# CCupPSU.net
KiCad netlist of a schematic drawn in EAGLE
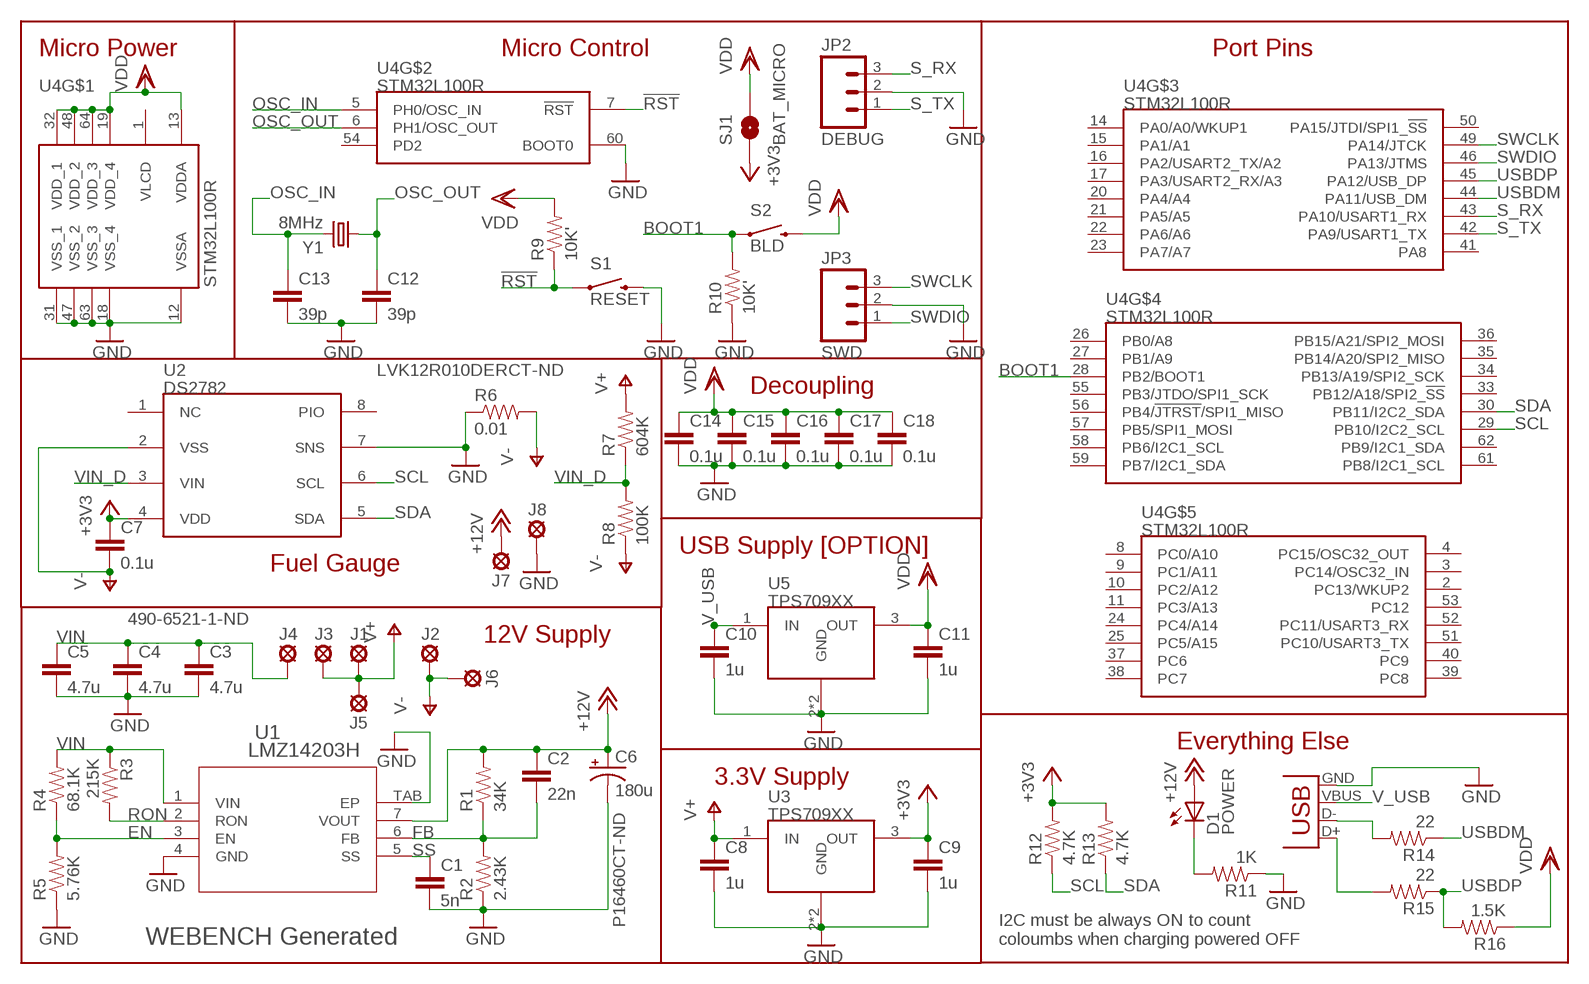
[diagram p0: schematic, sheet 1]

(export (version "E")
  (design (tool "Eeschema 10.0.6"))
  (components
    (comp (ref "C1")
      (value "5n")
      (footprint "eagle-import:1206")
      (libsource (lib "eagle-import") (part "CAP1206"))
    )
    (comp (ref "C2")
      (value "22n")
      (footprint "eagle-import:1206")
      (libsource (lib "eagle-import") (part "CAP1206"))
    )
    (comp (ref "C3")
      (value "4.7u")
      (footprint "eagle-import:1206")
      (libsource (lib "eagle-import") (part "CAP1206"))
    )
    (comp (ref "C4")
      (value "4.7u")
      (footprint "eagle-import:1206")
      (libsource (lib "eagle-import") (part "CAP1206"))
    )
    (comp (ref "C5")
      (value "4.7u")
      (footprint "eagle-import:1206")
      (libsource (lib "eagle-import") (part "CAP1206"))
    )
    (comp (ref "C6")
      (value "180u")
      (footprint "eagle-import:PANASONIC_E")
      (libsource (lib "eagle-import") (part "CAP_POLE"))
    )
    (comp (ref "C7")
      (value "0.1u")
      (footprint "eagle-import:1206")
      (libsource (lib "eagle-import") (part "CAP1206"))
    )
    (comp (ref "C8")
      (value "1u")
      (footprint "eagle-import:1206")
      (libsource (lib "eagle-import") (part "CAP1206"))
    )
    (comp (ref "C9")
      (value "1u")
      (footprint "eagle-import:1206")
      (libsource (lib "eagle-import") (part "CAP1206"))
    )
    (comp (ref "C10")
      (value "1u")
      (footprint "eagle-import:1206")
      (libsource (lib "eagle-import") (part "CAP1206"))
    )
    (comp (ref "C11")
      (value "1u")
      (footprint "eagle-import:1206")
      (libsource (lib "eagle-import") (part "CAP1206"))
    )
    (comp (ref "C12")
      (value "39p")
      (footprint "eagle-import:1206")
      (libsource (lib "eagle-import") (part "CAP1206"))
    )
    (comp (ref "C13")
      (value "39p")
      (footprint "eagle-import:1206")
      (libsource (lib "eagle-import") (part "CAP1206"))
    )
    (comp (ref "C14")
      (value "0.1u")
      (footprint "eagle-import:1206")
      (libsource (lib "eagle-import") (part "CAP1206"))
    )
    (comp (ref "C15")
      (value "0.1u")
      (footprint "eagle-import:1206")
      (libsource (lib "eagle-import") (part "CAP1206"))
    )
    (comp (ref "C16")
      (value "0.1u")
      (footprint "eagle-import:1206")
      (libsource (lib "eagle-import") (part "CAP1206"))
    )
    (comp (ref "C17")
      (value "0.1u")
      (footprint "eagle-import:1206")
      (libsource (lib "eagle-import") (part "CAP1206"))
    )
    (comp (ref "C18")
      (value "0.1u")
      (footprint "eagle-import:1206")
      (libsource (lib "eagle-import") (part "CAP1206"))
    )
    (comp (ref "D1")
      (value "POWER")
      (footprint "eagle-import:LED-1206")
      (libsource (lib "eagle-import") (part "LED-RED1206"))
    )
    (comp (ref "J1")
      (value "SE14")
      (footprint "eagle-import:SE14")
      (libsource (lib "eagle-import") (part "SE14"))
    )
    (comp (ref "J2")
      (value "SE14")
      (footprint "eagle-import:SE14")
      (libsource (lib "eagle-import") (part "SE14"))
    )
    (comp (ref "J3")
      (value "SE14")
      (footprint "eagle-import:SE14")
      (libsource (lib "eagle-import") (part "SE14"))
    )
    (comp (ref "J4")
      (value "SE14")
      (footprint "eagle-import:SE14")
      (libsource (lib "eagle-import") (part "SE14"))
    )
    (comp (ref "J5")
      (value "SE14")
      (footprint "eagle-import:SE14")
      (libsource (lib "eagle-import") (part "SE14"))
    )
    (comp (ref "J6")
      (value "SE14")
      (footprint "eagle-import:SE14")
      (libsource (lib "eagle-import") (part "SE14"))
    )
    (comp (ref "J7")
      (value "SE14")
      (footprint "eagle-import:SE14")
      (libsource (lib "eagle-import") (part "SE14"))
    )
    (comp (ref "J8")
      (value "SE14")
      (footprint "eagle-import:SE14")
      (libsource (lib "eagle-import") (part "SE14"))
    )
    (comp (ref "JP1")
      (value "USBSMD")
      (footprint "eagle-import:USB-MINIB")
      (libsource (lib "eagle-import") (part "USBSMD"))
    )
    (comp (ref "JP2")
      (value "DEBUG")
      (footprint "eagle-import:1X03")
      (libsource (lib "eagle-import") (part "M03PTH"))
    )
    (comp (ref "JP3")
      (value "SWD")
      (footprint "eagle-import:1X03")
      (libsource (lib "eagle-import") (part "M03PTH"))
    )
    (comp (ref "R1")
      (value "34K")
      (footprint "eagle-import:1206")
      (libsource (lib "eagle-import") (part "RESISTOR1206"))
    )
    (comp (ref "R2")
      (value "2.43K")
      (footprint "eagle-import:1206")
      (libsource (lib "eagle-import") (part "RESISTOR1206"))
    )
    (comp (ref "R3")
      (value "215K")
      (footprint "eagle-import:1206")
      (libsource (lib "eagle-import") (part "RESISTOR1206"))
    )
    (comp (ref "R4")
      (value "68.1K")
      (footprint "eagle-import:1206")
      (libsource (lib "eagle-import") (part "RESISTOR1206"))
    )
    (comp (ref "R5")
      (value "5.76K")
      (footprint "eagle-import:1206")
      (libsource (lib "eagle-import") (part "RESISTOR1206"))
    )
    (comp (ref "R6")
      (value "0.01")
      (footprint "eagle-import:1206")
      (libsource (lib "eagle-import") (part "RESISTOR1206"))
    )
    (comp (ref "R7")
      (value "604K")
      (footprint "eagle-import:1206")
      (libsource (lib "eagle-import") (part "RESISTOR1206"))
    )
    (comp (ref "R8")
      (value "100K")
      (footprint "eagle-import:1206")
      (libsource (lib "eagle-import") (part "RESISTOR1206"))
    )
    (comp (ref "R9")
      (value "10K'")
      (footprint "eagle-import:1206")
      (libsource (lib "eagle-import") (part "RESISTOR1206"))
    )
    (comp (ref "R10")
      (value "10K'")
      (footprint "eagle-import:1206")
      (libsource (lib "eagle-import") (part "RESISTOR1206"))
    )
    (comp (ref "R11")
      (value "1K")
      (footprint "eagle-import:1206")
      (libsource (lib "eagle-import") (part "RESISTOR1206"))
    )
    (comp (ref "R12")
      (value "4.7K")
      (footprint "eagle-import:1206")
      (libsource (lib "eagle-import") (part "RESISTOR1206"))
    )
    (comp (ref "R13")
      (value "4.7K")
      (footprint "eagle-import:1206")
      (libsource (lib "eagle-import") (part "RESISTOR1206"))
    )
    (comp (ref "R14")
      (value "22")
      (footprint "eagle-import:1206")
      (libsource (lib "eagle-import") (part "RES1206"))
    )
    (comp (ref "R15")
      (value "22")
      (footprint "eagle-import:1206")
      (libsource (lib "eagle-import") (part "RES1206"))
    )
    (comp (ref "R16")
      (value "1.5K")
      (footprint "eagle-import:1206")
      (libsource (lib "eagle-import") (part "RES1206"))
    )
    (comp (ref "S1")
      (value "RESET")
      (footprint "eagle-import:TACTILE-PTH")
      (libsource (lib "eagle-import") (part "SWITCH-MOMENTARY-2PTH"))
    )
    (comp (ref "S2")
      (value "BLD")
      (footprint "eagle-import:TACTILE-PTH")
      (libsource (lib "eagle-import") (part "SWITCH-MOMENTARY-2PTH"))
    )
    (comp (ref "SJ1")
      (value "BAT_MICRO")
      (footprint "eagle-import:SJ_2S-TRACE")
      (libsource (lib "eagle-import") (part "SOLDERJUMPERTRACE"))
    )
    (comp (ref "U1")
      (value "LMZ14203H")
      (footprint "eagle-import:TZA07A")
      (fields
        (field (name "MANUFACTURER") "Texas Instruments")
        (field (name "MANUFACTURER_PART_NUMBER") "lmz14203h_ndw_7")
      )
      (libsource (lib "eagle-import") (part "LMZ14203H"))
    )
    (comp (ref "U2")
      (value "DS2782")
      (footprint "eagle-import:TSSOP8")
      (libsource (lib "eagle-import") (part "DS2782"))
    )
    (comp (ref "U3")
      (value "TPS709XX")
      (footprint "eagle-import:SOT223")
      (libsource (lib "eagle-import") (part "TPS709XX"))
    )
    (comp (ref "U4")
      (value "STM32L100R")
      (footprint "eagle-import:TQFP64")
      (libsource (lib "eagle-import") (part "STM32L100R"))
    )
    (comp (ref "U5")
      (value "TPS709XX")
      (footprint "eagle-import:SOT223")
      (libsource (lib "eagle-import") (part "TPS709XX"))
    )
    (comp (ref "Y1")
      (value "8MHz")
      (footprint "eagle-import:HC49US")
      (libsource (lib "eagle-import") (part "CRYSTALHC49US"))
    )
  )
  (nets
    (net (code "1") (name "+3V3") (class "Default")
      (node (ref "C7") (pin "1") (pinfunction "1_1") (pintype "passive"))
      (node (ref "C9") (pin "1") (pinfunction "1_1") (pintype "passive"))
      (node (ref "R12") (pin "2") (pinfunction "2_2") (pintype "passive"))
      (node (ref "R13") (pin "2") (pinfunction "2_2") (pintype "passive"))
      (node (ref "SJ1") (pin "1") (pinfunction "1_1") (pintype "passive"))
      (node (ref "U2") (pin "4") (pinfunction "VDD_4") (pintype "power_in"))
      (node (ref "U3") (pin "3") (pinfunction "OUT_3") (pintype "power_in"))
    )
    (net (code "2") (name "+12V") (class "Default")
      (node (ref "C2") (pin "1") (pinfunction "1_1") (pintype "passive"))
      (node (ref "C6") (pin "+") (pinfunction "+_+") (pintype "passive"))
      (node (ref "D1") (pin "A") (pinfunction "A_A") (pintype "passive"))
      (node (ref "J7") (pin "MP") (pinfunction "MP_MP") (pintype "passive"))
      (node (ref "R1") (pin "2") (pinfunction "2_2") (pintype "passive"))
      (node (ref "U1") (pin "7") (pinfunction "VOUT_7") (pintype "power_in"))
    )
    (net (code "3") (name "/BOOT1") (class "Default")
      (node (ref "R10") (pin "2") (pinfunction "2_2") (pintype "passive"))
      (node (ref "S2") (pin "1") (pinfunction "1_1") (pintype "passive"))
      (node (ref "U4") (pin "28") (pinfunction "PB2/BOOT1_28") (pintype "bidirectional"))
    )
    (net (code "4") (name "/EN") (class "Default")
      (node (ref "R4") (pin "1") (pinfunction "1_1") (pintype "passive"))
      (node (ref "R5") (pin "2") (pinfunction "2_2") (pintype "passive"))
      (node (ref "U1") (pin "3") (pinfunction "EN_3") (pintype "input"))
    )
    (net (code "5") (name "/FB") (class "Default")
      (node (ref "C2") (pin "2") (pinfunction "2_2") (pintype "passive"))
      (node (ref "R1") (pin "1") (pinfunction "1_1") (pintype "passive"))
      (node (ref "R2") (pin "2") (pinfunction "2_2") (pintype "passive"))
      (node (ref "U1") (pin "6") (pinfunction "FB_6") (pintype "output"))
    )
    (net (code "6") (name "/OSC_IN") (class "Default")
      (node (ref "C13") (pin "1") (pinfunction "1_1") (pintype "passive"))
      (node (ref "U4") (pin "5") (pinfunction "PH0/OSC_IN_5") (pintype "bidirectional"))
      (node (ref "Y1") (pin "2") (pinfunction "2_2") (pintype "passive"))
    )
    (net (code "7") (name "/OSC_OUT") (class "Default")
      (node (ref "C12") (pin "1") (pinfunction "1_1") (pintype "passive"))
      (node (ref "U4") (pin "6") (pinfunction "PH1/OSC_OUT_6") (pintype "bidirectional"))
      (node (ref "Y1") (pin "1") (pinfunction "1_1") (pintype "passive"))
    )
    (net (code "8") (name "/RON") (class "Default")
      (node (ref "R3") (pin "2") (pinfunction "2_2") (pintype "passive"))
      (node (ref "U1") (pin "2") (pinfunction "RON_2") (pintype "passive"))
    )
    (net (code "9") (name "/SCL") (class "Default")
      (node (ref "R12") (pin "1") (pinfunction "1_1") (pintype "passive"))
      (node (ref "U2") (pin "6") (pinfunction "SCL_6") (pintype "bidirectional"))
      (node (ref "U4") (pin "29") (pinfunction "PB10/I2C2_SCL_29") (pintype "bidirectional"))
    )
    (net (code "10") (name "/SDA") (class "Default")
      (node (ref "R13") (pin "1") (pinfunction "1_1") (pintype "passive"))
      (node (ref "U2") (pin "5") (pinfunction "SDA_5") (pintype "bidirectional"))
      (node (ref "U4") (pin "30") (pinfunction "PB11/I2C2_SDA_30") (pintype "bidirectional"))
    )
    (net (code "11") (name "/SS") (class "Default")
      (node (ref "C1") (pin "1") (pinfunction "1_1") (pintype "passive"))
      (node (ref "U1") (pin "5") (pinfunction "SS_5") (pintype "passive"))
    )
    (net (code "12") (name "/SWCLK") (class "Default")
      (node (ref "JP3") (pin "3") (pinfunction "3_3") (pintype "passive"))
      (node (ref "U4") (pin "49") (pinfunction "PA14/JTCK_49") (pintype "bidirectional"))
    )
    (net (code "13") (name "/SWDIO") (class "Default")
      (node (ref "JP3") (pin "1") (pinfunction "1_1") (pintype "passive"))
      (node (ref "U4") (pin "46") (pinfunction "PA13/JTMS_46") (pintype "bidirectional"))
    )
    (net (code "14") (name "/S_RX") (class "Default")
      (node (ref "JP2") (pin "3") (pinfunction "3_3") (pintype "passive"))
      (node (ref "U4") (pin "43") (pinfunction "PA10/USART1_RX_43") (pintype "bidirectional"))
    )
    (net (code "15") (name "/S_TX") (class "Default")
      (node (ref "JP2") (pin "1") (pinfunction "1_1") (pintype "passive"))
      (node (ref "U4") (pin "42") (pinfunction "PA9/USART1_TX_42") (pintype "bidirectional"))
    )
    (net (code "16") (name "/USBDM") (class "Default")
      (node (ref "R14") (pin "1") (pinfunction "1_1") (pintype "passive"))
      (node (ref "U4") (pin "44") (pinfunction "PA11/USB_DM_44") (pintype "bidirectional"))
    )
    (net (code "17") (name "/USBDP") (class "Default")
      (node (ref "R15") (pin "1") (pinfunction "1_1") (pintype "passive"))
      (node (ref "R16") (pin "2") (pinfunction "2_2") (pintype "passive"))
      (node (ref "U4") (pin "45") (pinfunction "PA12/USB_DP_45") (pintype "bidirectional"))
    )
    (net (code "18") (name "/VIN") (class "Default")
      (node (ref "C3") (pin "1") (pinfunction "1_1") (pintype "passive"))
      (node (ref "C4") (pin "1") (pinfunction "1_1") (pintype "passive"))
      (node (ref "C5") (pin "1") (pinfunction "1_1") (pintype "passive"))
      (node (ref "J4") (pin "MP") (pinfunction "MP_MP") (pintype "passive"))
      (node (ref "R3") (pin "1") (pinfunction "1_1") (pintype "passive"))
      (node (ref "R4") (pin "2") (pinfunction "2_2") (pintype "passive"))
      (node (ref "U1") (pin "1") (pinfunction "VIN_1") (pintype "input"))
    )
    (net (code "19") (name "/VIN_D") (class "Default")
      (node (ref "R7") (pin "1") (pinfunction "1_1") (pintype "passive"))
      (node (ref "R8") (pin "2") (pinfunction "2_2") (pintype "passive"))
      (node (ref "U2") (pin "3") (pinfunction "VIN_3") (pintype "passive"))
    )
    (net (code "20") (name "/V_USB") (class "Default")
      (node (ref "C10") (pin "1") (pinfunction "1_1") (pintype "passive"))
      (node (ref "JP1") (pin "VBUS") (pinfunction "VBUS_VBUS") (pintype "bidirectional"))
      (node (ref "U5") (pin "1") (pinfunction "IN_1") (pintype "power_in"))
    )
    (net (code "21") (name "/~{RST}") (class "Default")
      (node (ref "R9") (pin "1") (pinfunction "1_1") (pintype "passive"))
      (node (ref "S1") (pin "1") (pinfunction "1_1") (pintype "passive"))
      (node (ref "U4") (pin "7") (pinfunction "~{RST}_7") (pintype "input"))
    )
    (net (code "22") (name "GND") (class "Default")
      (node (ref "C1") (pin "2") (pinfunction "2_2") (pintype "passive"))
      (node (ref "C10") (pin "2") (pinfunction "2_2") (pintype "passive"))
      (node (ref "C11") (pin "2") (pinfunction "2_2") (pintype "passive"))
      (node (ref "C12") (pin "2") (pinfunction "2_2") (pintype "passive"))
      (node (ref "C13") (pin "2") (pinfunction "2_2") (pintype "passive"))
      (node (ref "C14") (pin "2") (pinfunction "2_2") (pintype "passive"))
      (node (ref "C15") (pin "2") (pinfunction "2_2") (pintype "passive"))
      (node (ref "C16") (pin "2") (pinfunction "2_2") (pintype "passive"))
      (node (ref "C17") (pin "2") (pinfunction "2_2") (pintype "passive"))
      (node (ref "C18") (pin "2") (pinfunction "2_2") (pintype "passive"))
      (node (ref "C3") (pin "2") (pinfunction "2_2") (pintype "passive"))
      (node (ref "C4") (pin "2") (pinfunction "2_2") (pintype "passive"))
      (node (ref "C5") (pin "2") (pinfunction "2_2") (pintype "passive"))
      (node (ref "C6") (pin "-") (pinfunction "-_-") (pintype "passive"))
      (node (ref "C8") (pin "2") (pinfunction "2_2") (pintype "passive"))
      (node (ref "C9") (pin "2") (pinfunction "2_2") (pintype "passive"))
      (node (ref "J8") (pin "MP") (pinfunction "MP_MP") (pintype "passive"))
      (node (ref "JP1") (pin "GND") (pinfunction "GND_GND") (pintype "bidirectional"))
      (node (ref "JP2") (pin "2") (pinfunction "2_2") (pintype "passive"))
      (node (ref "JP3") (pin "2") (pinfunction "2_2") (pintype "passive"))
      (node (ref "R10") (pin "1") (pinfunction "1_1") (pintype "passive"))
      (node (ref "R11") (pin "1") (pinfunction "1_1") (pintype "passive"))
      (node (ref "R2") (pin "1") (pinfunction "1_1") (pintype "passive"))
      (node (ref "R5") (pin "1") (pinfunction "1_1") (pintype "passive"))
      (node (ref "R6") (pin "1") (pinfunction "1_1") (pintype "passive"))
      (node (ref "S1") (pin "3") (pinfunction "2_3") (pintype "passive"))
      (node (ref "U1") (pin "4") (pinfunction "GND_4") (pintype "power_in"))
      (node (ref "U1") (pin "TAB") (pinfunction "EP_TAB") (pintype "passive"))
      (node (ref "U2") (pin "7") (pinfunction "SNS_7") (pintype "input"))
      (node (ref "U3") (pin "2") (pinfunction "GND_2") (pintype "power_in"))
      (node (ref "U3") (pin "4") (pinfunction "GND_4") (pintype "power_in"))
      (node (ref "U4") (pin "12") (pinfunction "VSSA_12") (pintype "power_in"))
      (node (ref "U4") (pin "18") (pinfunction "VSS_4_18") (pintype "power_in"))
      (node (ref "U4") (pin "31") (pinfunction "VSS_1_31") (pintype "power_in"))
      (node (ref "U4") (pin "47") (pinfunction "VSS_2_47") (pintype "power_in"))
      (node (ref "U4") (pin "60") (pinfunction "BOOT0_60") (pintype "input"))
      (node (ref "U4") (pin "63") (pinfunction "VSS_3_63") (pintype "power_in"))
      (node (ref "U5") (pin "2") (pinfunction "GND_2") (pintype "power_in"))
      (node (ref "U5") (pin "4") (pinfunction "GND_4") (pintype "power_in"))
    )
    (net (code "23") (name "Net-(D1-PadC)") (class "Default")
      (node (ref "D1") (pin "C") (pinfunction "C_C") (pintype "passive"))
      (node (ref "R11") (pin "2") (pinfunction "2_2") (pintype "passive"))
    )
    (net (code "24") (name "Net-(JP1-PadD+)") (class "Default")
      (node (ref "JP1") (pin "D+") (pinfunction "D+_D+") (pintype "bidirectional"))
      (node (ref "R15") (pin "2") (pinfunction "2_2") (pintype "passive"))
    )
    (net (code "25") (name "Net-(JP1-PadD-)") (class "Default")
      (node (ref "JP1") (pin "D-") (pinfunction "D-_D-") (pintype "bidirectional"))
      (node (ref "R14") (pin "2") (pinfunction "2_2") (pintype "passive"))
    )
    (net (code "26") (name "V+") (class "Default")
      (node (ref "C8") (pin "1") (pinfunction "1_1") (pintype "passive"))
      (node (ref "J1") (pin "MP") (pinfunction "MP_MP") (pintype "passive"))
      (node (ref "J3") (pin "MP") (pinfunction "MP_MP") (pintype "passive"))
      (node (ref "J5") (pin "MP") (pinfunction "MP_MP") (pintype "passive"))
      (node (ref "R7") (pin "2") (pinfunction "2_2") (pintype "passive"))
      (node (ref "U3") (pin "1") (pinfunction "IN_1") (pintype "power_in"))
    )
    (net (code "27") (name "V-") (class "Default")
      (node (ref "C7") (pin "2") (pinfunction "2_2") (pintype "passive"))
      (node (ref "J2") (pin "MP") (pinfunction "MP_MP") (pintype "passive"))
      (node (ref "J6") (pin "MP") (pinfunction "MP_MP") (pintype "passive"))
      (node (ref "R6") (pin "2") (pinfunction "2_2") (pintype "passive"))
      (node (ref "R8") (pin "1") (pinfunction "1_1") (pintype "passive"))
      (node (ref "U2") (pin "2") (pinfunction "VSS_2") (pintype "power_in"))
    )
    (net (code "28") (name "VDD") (class "Default")
      (node (ref "C11") (pin "1") (pinfunction "1_1") (pintype "passive"))
      (node (ref "C14") (pin "1") (pinfunction "1_1") (pintype "passive"))
      (node (ref "C15") (pin "1") (pinfunction "1_1") (pintype "passive"))
      (node (ref "C16") (pin "1") (pinfunction "1_1") (pintype "passive"))
      (node (ref "C17") (pin "1") (pinfunction "1_1") (pintype "passive"))
      (node (ref "C18") (pin "1") (pinfunction "1_1") (pintype "passive"))
      (node (ref "R16") (pin "1") (pinfunction "1_1") (pintype "passive"))
      (node (ref "R9") (pin "2") (pinfunction "2_2") (pintype "passive"))
      (node (ref "S2") (pin "3") (pinfunction "2_3") (pintype "passive"))
      (node (ref "SJ1") (pin "2") (pinfunction "2_2") (pintype "passive"))
      (node (ref "U4") (pin "13") (pinfunction "VDDA_13") (pintype "power_in"))
      (node (ref "U4") (pin "19") (pinfunction "VDD_4_19") (pintype "power_in"))
      (node (ref "U4") (pin "32") (pinfunction "VDD_1_32") (pintype "power_in"))
      (node (ref "U4") (pin "48") (pinfunction "VDD_2_48") (pintype "power_in"))
      (node (ref "U4") (pin "64") (pinfunction "VDD_3_64") (pintype "power_in"))
      (node (ref "U5") (pin "3") (pinfunction "OUT_3") (pintype "power_in"))
    )
    (net (code "29") (name "unconnected-(U2-NC-Pad1)") (class "Default")
      (node (ref "U2") (pin "1") (pinfunction "NC_1") (pintype "no_connect"))
    )
    (net (code "30") (name "unconnected-(U2-PIO-Pad8)") (class "Default")
      (node (ref "U2") (pin "8") (pinfunction "PIO_8") (pintype "output"))
    )
    (net (code "31") (name "unconnected-(U4A-VLCD-Pad1)") (class "Default")
      (node (ref "U4") (pin "1") (pinfunction "VLCD_1") (pintype "output"))
    )
    (net (code "32") (name "unconnected-(U4B-PD2-Pad54)") (class "Default")
      (node (ref "U4") (pin "54") (pinfunction "PD2_54") (pintype "bidirectional"))
    )
    (net (code "33") (name "unconnected-(U4C-PA0{slash}A0{slash}WKUP1-Pad14)") (class "Default")
      (node (ref "U4") (pin "14") (pinfunction "PA0/A0/WKUP1_14") (pintype "bidirectional"))
    )
    (net (code "34") (name "unconnected-(U4C-PA1{slash}A1-Pad15)") (class "Default")
      (node (ref "U4") (pin "15") (pinfunction "PA1/A1_15") (pintype "bidirectional"))
    )
    (net (code "35") (name "unconnected-(U4C-PA2{slash}USART2_TX{slash}A2-Pad16)") (class "Default")
      (node (ref "U4") (pin "16") (pinfunction "PA2/USART2_TX/A2_16") (pintype "bidirectional"))
    )
    (net (code "36") (name "unconnected-(U4C-PA3{slash}USART2_RX{slash}A3-Pad17)") (class "Default")
      (node (ref "U4") (pin "17") (pinfunction "PA3/USART2_RX/A3_17") (pintype "bidirectional"))
    )
    (net (code "37") (name "unconnected-(U4C-PA4{slash}A4-Pad20)") (class "Default")
      (node (ref "U4") (pin "20") (pinfunction "PA4/A4_20") (pintype "bidirectional"))
    )
    (net (code "38") (name "unconnected-(U4C-PA5{slash}A5-Pad21)") (class "Default")
      (node (ref "U4") (pin "21") (pinfunction "PA5/A5_21") (pintype "bidirectional"))
    )
    (net (code "39") (name "unconnected-(U4C-PA6{slash}A6-Pad22)") (class "Default")
      (node (ref "U4") (pin "22") (pinfunction "PA6/A6_22") (pintype "bidirectional"))
    )
    (net (code "40") (name "unconnected-(U4C-PA7{slash}A7-Pad23)") (class "Default")
      (node (ref "U4") (pin "23") (pinfunction "PA7/A7_23") (pintype "bidirectional"))
    )
    (net (code "41") (name "unconnected-(U4C-PA8-Pad41)") (class "Default")
      (node (ref "U4") (pin "41") (pinfunction "PA8_41") (pintype "bidirectional"))
    )
    (net (code "42") (name "unconnected-(U4C-PA15{slash}JTDI{slash}SPI1_~{SS}-Pad50)") (class "Default")
      (node (ref "U4") (pin "50") (pinfunction "PA15/JTDI/SPI1_~{SS}_50") (pintype "bidirectional"))
    )
    (net (code "43") (name "unconnected-(U4D-PB0{slash}A8-Pad26)") (class "Default")
      (node (ref "U4") (pin "26") (pinfunction "PB0/A8_26") (pintype "bidirectional"))
    )
    (net (code "44") (name "unconnected-(U4D-PB1{slash}A9-Pad27)") (class "Default")
      (node (ref "U4") (pin "27") (pinfunction "PB1/A9_27") (pintype "bidirectional"))
    )
    (net (code "45") (name "unconnected-(U4D-PB3{slash}JTDO{slash}SPI1_SCK-Pad55)") (class "Default")
      (node (ref "U4") (pin "55") (pinfunction "PB3/JTDO/SPI1_SCK_55") (pintype "bidirectional"))
    )
    (net (code "46") (name "unconnected-(U4D-PB4{slash}~{JTRST}{slash}SPI1_MISO-Pad56)") (class "Default")
      (node (ref "U4") (pin "56") (pinfunction "PB4/~{JTRST}/SPI1_MISO_56") (pintype "bidirectional"))
    )
    (net (code "47") (name "unconnected-(U4D-PB5{slash}SPI1_MOSI-Pad57)") (class "Default")
      (node (ref "U4") (pin "57") (pinfunction "PB5/SPI1_MOSI_57") (pintype "bidirectional"))
    )
    (net (code "48") (name "unconnected-(U4D-PB6{slash}I2C1_SCL-Pad58)") (class "Default")
      (node (ref "U4") (pin "58") (pinfunction "PB6/I2C1_SCL_58") (pintype "bidirectional"))
    )
    (net (code "49") (name "unconnected-(U4D-PB7{slash}I2C1_SDA-Pad59)") (class "Default")
      (node (ref "U4") (pin "59") (pinfunction "PB7/I2C1_SDA_59") (pintype "bidirectional"))
    )
    (net (code "50") (name "unconnected-(U4D-PB8{slash}I2C1_SCL-Pad61)") (class "Default")
      (node (ref "U4") (pin "61") (pinfunction "PB8/I2C1_SCL_61") (pintype "bidirectional"))
    )
    (net (code "51") (name "unconnected-(U4D-PB9{slash}I2C1_SDA-Pad62)") (class "Default")
      (node (ref "U4") (pin "62") (pinfunction "PB9/I2C1_SDA_62") (pintype "bidirectional"))
    )
    (net (code "52") (name "unconnected-(U4D-PB12{slash}A18{slash}SPI2_~{SS}-Pad33)") (class "Default")
      (node (ref "U4") (pin "33") (pinfunction "PB12/A18/SPI2_~{SS}_33") (pintype "bidirectional"))
    )
    (net (code "53") (name "unconnected-(U4D-PB13{slash}A19{slash}SPI2_SCK-Pad34)") (class "Default")
      (node (ref "U4") (pin "34") (pinfunction "PB13/A19/SPI2_SCK_34") (pintype "bidirectional"))
    )
    (net (code "54") (name "unconnected-(U4D-PB14{slash}A20{slash}SPI2_MISO-Pad35)") (class "Default")
      (node (ref "U4") (pin "35") (pinfunction "PB14/A20/SPI2_MISO_35") (pintype "bidirectional"))
    )
    (net (code "55") (name "unconnected-(U4D-PB15{slash}A21{slash}SPI2_MOSI-Pad36)") (class "Default")
      (node (ref "U4") (pin "36") (pinfunction "PB15/A21/SPI2_MOSI_36") (pintype "bidirectional"))
    )
    (net (code "56") (name "unconnected-(U4E-PC0{slash}A10-Pad8)") (class "Default")
      (node (ref "U4") (pin "8") (pinfunction "PC0/A10_8") (pintype "bidirectional"))
    )
    (net (code "57") (name "unconnected-(U4E-PC1{slash}A11-Pad9)") (class "Default")
      (node (ref "U4") (pin "9") (pinfunction "PC1/A11_9") (pintype "bidirectional"))
    )
    (net (code "58") (name "unconnected-(U4E-PC2{slash}A12-Pad10)") (class "Default")
      (node (ref "U4") (pin "10") (pinfunction "PC2/A12_10") (pintype "bidirectional"))
    )
    (net (code "59") (name "unconnected-(U4E-PC3{slash}A13-Pad11)") (class "Default")
      (node (ref "U4") (pin "11") (pinfunction "PC3/A13_11") (pintype "bidirectional"))
    )
    (net (code "60") (name "unconnected-(U4E-PC4{slash}A14-Pad24)") (class "Default")
      (node (ref "U4") (pin "24") (pinfunction "PC4/A14_24") (pintype "bidirectional"))
    )
    (net (code "61") (name "unconnected-(U4E-PC5{slash}A15-Pad25)") (class "Default")
      (node (ref "U4") (pin "25") (pinfunction "PC5/A15_25") (pintype "bidirectional"))
    )
    (net (code "62") (name "unconnected-(U4E-PC6-Pad37)") (class "Default")
      (node (ref "U4") (pin "37") (pinfunction "PC6_37") (pintype "bidirectional"))
    )
    (net (code "63") (name "unconnected-(U4E-PC7-Pad38)") (class "Default")
      (node (ref "U4") (pin "38") (pinfunction "PC7_38") (pintype "bidirectional"))
    )
    (net (code "64") (name "unconnected-(U4E-PC8-Pad39)") (class "Default")
      (node (ref "U4") (pin "39") (pinfunction "PC8_39") (pintype "bidirectional"))
    )
    (net (code "65") (name "unconnected-(U4E-PC9-Pad40)") (class "Default")
      (node (ref "U4") (pin "40") (pinfunction "PC9_40") (pintype "bidirectional"))
    )
    (net (code "66") (name "unconnected-(U4E-PC10{slash}USART3_TX-Pad51)") (class "Default")
      (node (ref "U4") (pin "51") (pinfunction "PC10/USART3_TX_51") (pintype "bidirectional"))
    )
    (net (code "67") (name "unconnected-(U4E-PC11{slash}USART3_RX-Pad52)") (class "Default")
      (node (ref "U4") (pin "52") (pinfunction "PC11/USART3_RX_52") (pintype "bidirectional"))
    )
    (net (code "68") (name "unconnected-(U4E-PC12-Pad53)") (class "Default")
      (node (ref "U4") (pin "53") (pinfunction "PC12_53") (pintype "bidirectional"))
    )
    (net (code "69") (name "unconnected-(U4E-PC13{slash}WKUP2-Pad2)") (class "Default")
      (node (ref "U4") (pin "2") (pinfunction "PC13/WKUP2_2") (pintype "bidirectional"))
    )
    (net (code "70") (name "unconnected-(U4E-PC14{slash}OSC32_IN-Pad3)") (class "Default")
      (node (ref "U4") (pin "3") (pinfunction "PC14/OSC32_IN_3") (pintype "bidirectional"))
    )
    (net (code "71") (name "unconnected-(U4E-PC15{slash}OSC32_OUT-Pad4)") (class "Default")
      (node (ref "U4") (pin "4") (pinfunction "PC15/OSC32_OUT_4") (pintype "bidirectional"))
    )
  )
)
